# swbox_main.net
KiCad netlist of a schematic drawn in EAGLE
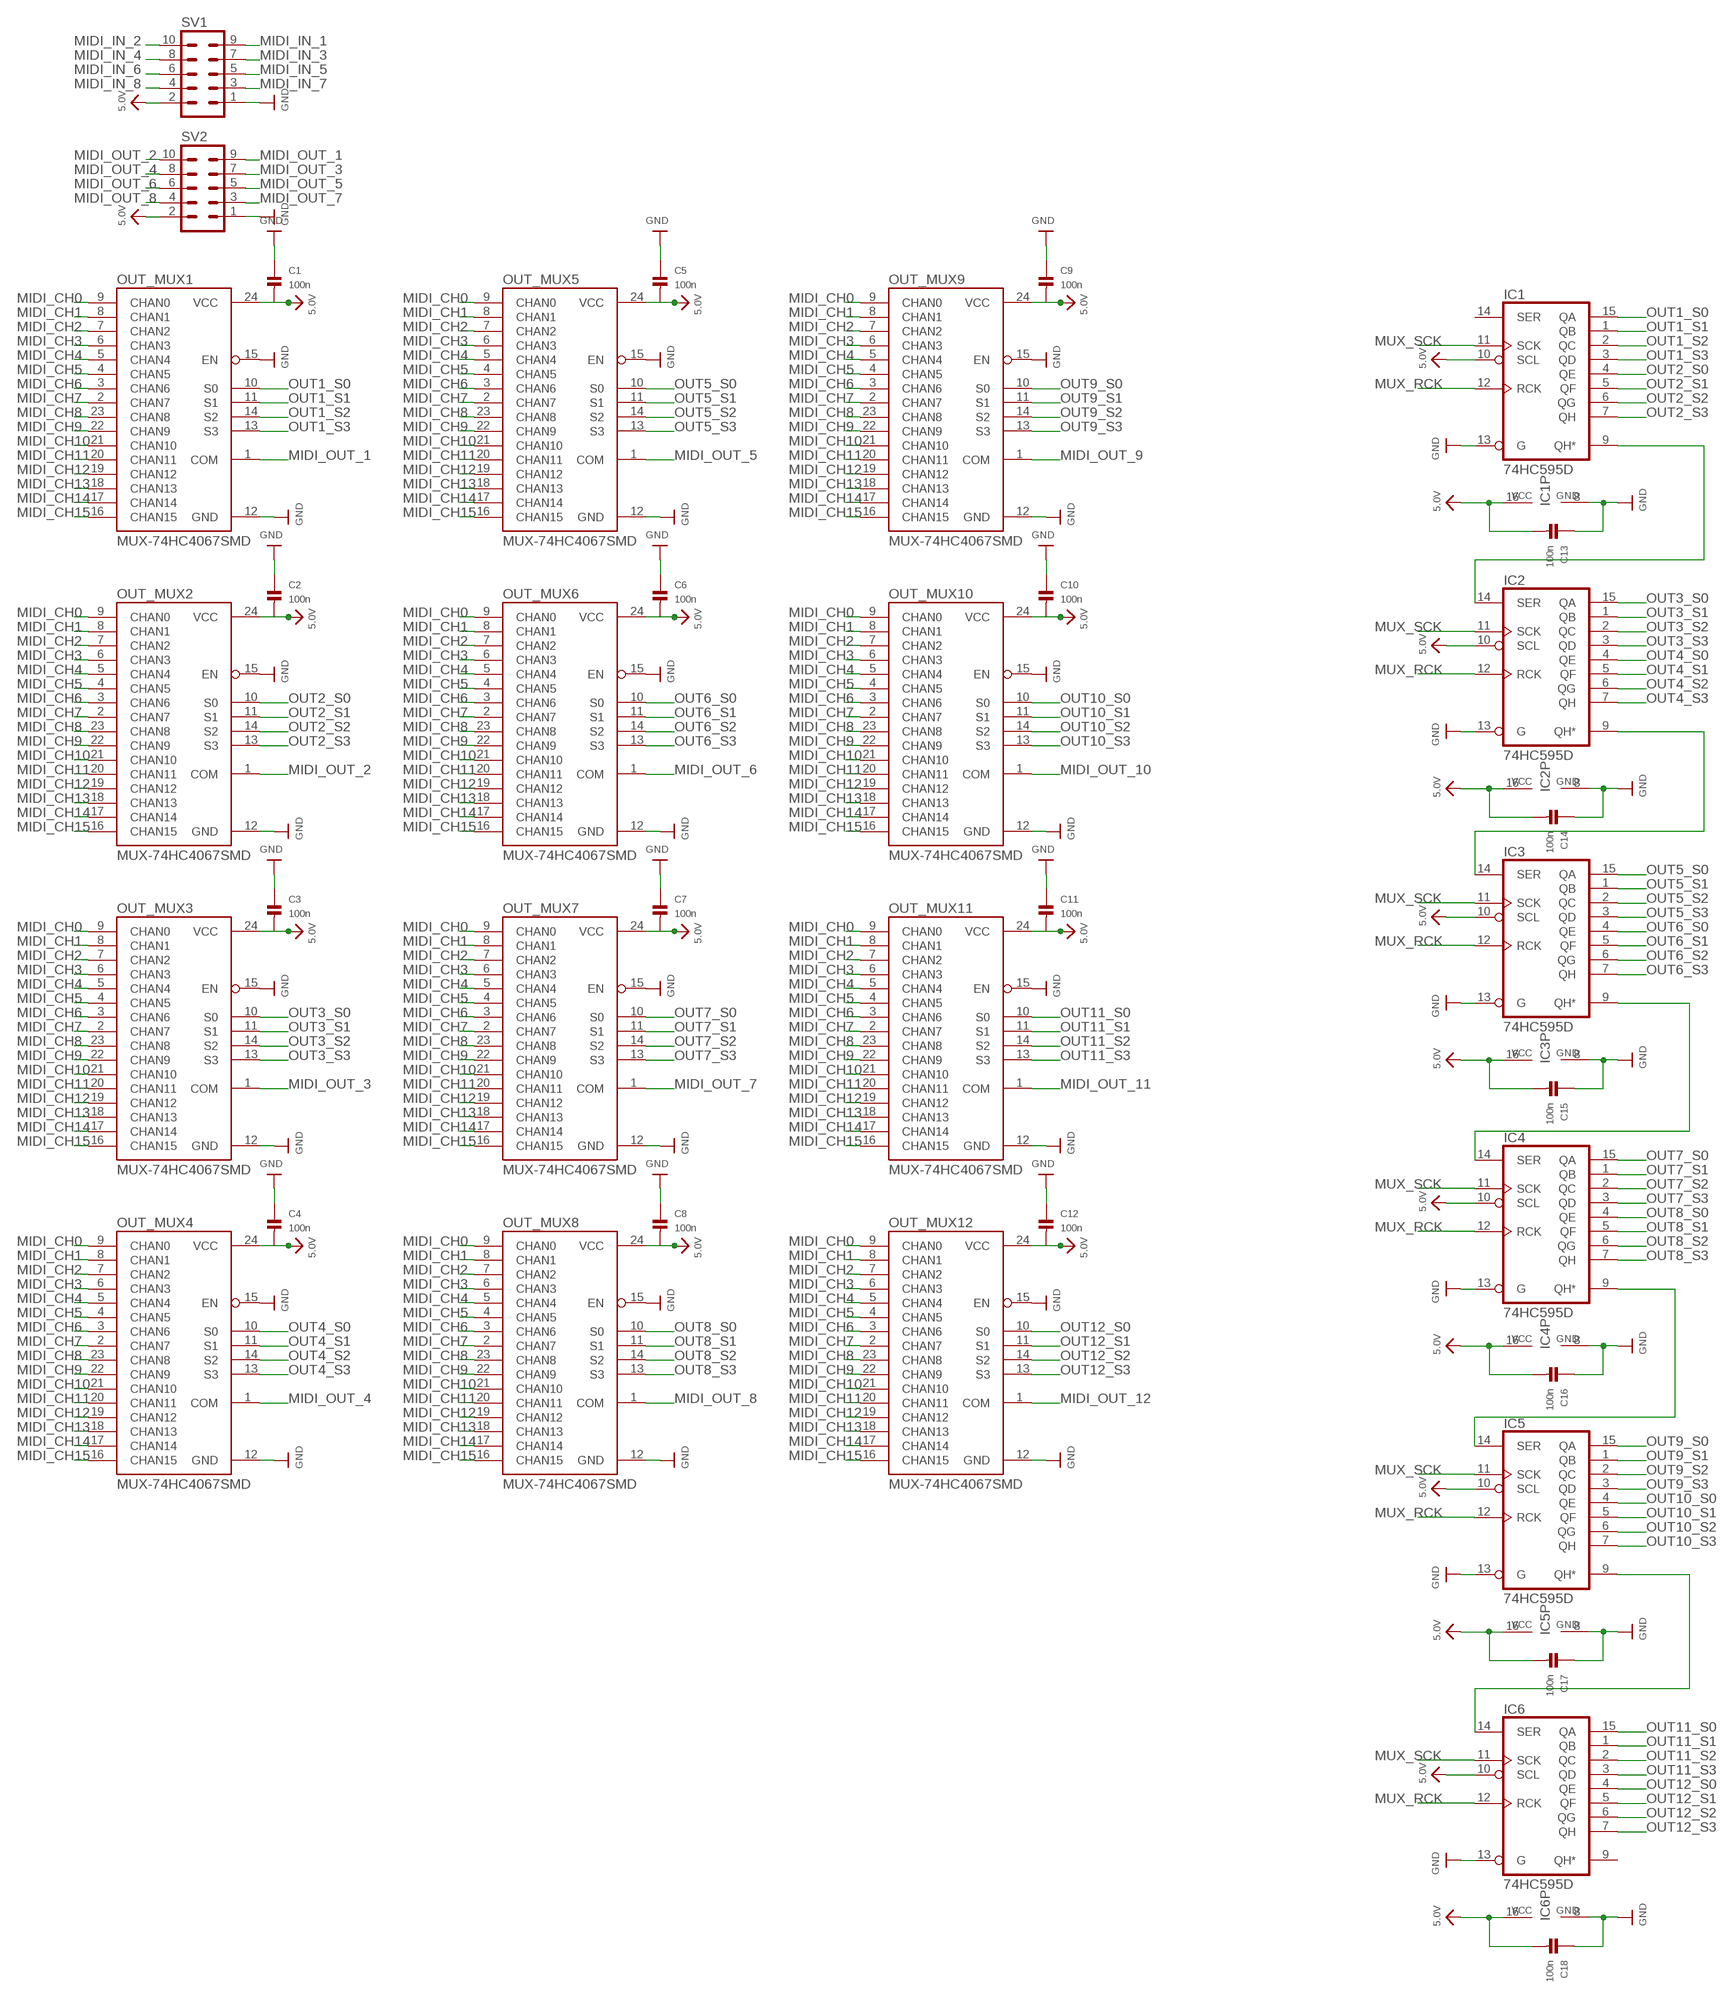
[diagram p0: schematic, sheet 1]

(export (version "E")
  (design (tool "Eeschema 10.0.6"))
  (components
    (comp (ref "C1")
      (value "100n")
      (footprint "eagle-import:0603")
      (libsource (lib "eagle-import") (part "CAP_CERAMIC0603"))
    )
    (comp (ref "C2")
      (value "100n")
      (footprint "eagle-import:0603")
      (libsource (lib "eagle-import") (part "CAP_CERAMIC0603"))
    )
    (comp (ref "C3")
      (value "100n")
      (footprint "eagle-import:0603")
      (libsource (lib "eagle-import") (part "CAP_CERAMIC0603"))
    )
    (comp (ref "C4")
      (value "100n")
      (footprint "eagle-import:0603")
      (libsource (lib "eagle-import") (part "CAP_CERAMIC0603"))
    )
    (comp (ref "C5")
      (value "100n")
      (footprint "eagle-import:0603")
      (libsource (lib "eagle-import") (part "CAP_CERAMIC0603"))
    )
    (comp (ref "C6")
      (value "100n")
      (footprint "eagle-import:0603")
      (libsource (lib "eagle-import") (part "CAP_CERAMIC0603"))
    )
    (comp (ref "C7")
      (value "100n")
      (footprint "eagle-import:0603")
      (libsource (lib "eagle-import") (part "CAP_CERAMIC0603"))
    )
    (comp (ref "C8")
      (value "100n")
      (footprint "eagle-import:0603")
      (libsource (lib "eagle-import") (part "CAP_CERAMIC0603"))
    )
    (comp (ref "C9")
      (value "100n")
      (footprint "eagle-import:0603")
      (libsource (lib "eagle-import") (part "CAP_CERAMIC0603"))
    )
    (comp (ref "C10")
      (value "100n")
      (footprint "eagle-import:0603")
      (libsource (lib "eagle-import") (part "CAP_CERAMIC0603"))
    )
    (comp (ref "C11")
      (value "100n")
      (footprint "eagle-import:0603")
      (libsource (lib "eagle-import") (part "CAP_CERAMIC0603"))
    )
    (comp (ref "C12")
      (value "100n")
      (footprint "eagle-import:0603")
      (libsource (lib "eagle-import") (part "CAP_CERAMIC0603"))
    )
    (comp (ref "C13")
      (value "100n")
      (footprint "eagle-import:0603")
      (libsource (lib "eagle-import") (part "CAP_CERAMIC0603"))
    )
    (comp (ref "C14")
      (value "100n")
      (footprint "eagle-import:0603")
      (libsource (lib "eagle-import") (part "CAP_CERAMIC0603"))
    )
    (comp (ref "C15")
      (value "100n")
      (footprint "eagle-import:0603")
      (libsource (lib "eagle-import") (part "CAP_CERAMIC0603"))
    )
    (comp (ref "C16")
      (value "100n")
      (footprint "eagle-import:0603")
      (libsource (lib "eagle-import") (part "CAP_CERAMIC0603"))
    )
    (comp (ref "C17")
      (value "100n")
      (footprint "eagle-import:0603")
      (libsource (lib "eagle-import") (part "CAP_CERAMIC0603"))
    )
    (comp (ref "C18")
      (value "100n")
      (footprint "eagle-import:0603")
      (libsource (lib "eagle-import") (part "CAP_CERAMIC0603"))
    )
    (comp (ref "IC1")
      (value "74HC595D")
      (footprint "eagle-import:SO16")
      (libsource (lib "eagle-import") (part "74595DHC"))
    )
    (comp (ref "IC2")
      (value "74HC595D")
      (footprint "eagle-import:SO16")
      (libsource (lib "eagle-import") (part "74595DHC"))
    )
    (comp (ref "IC3")
      (value "74HC595D")
      (footprint "eagle-import:SO16")
      (libsource (lib "eagle-import") (part "74595DHC"))
    )
    (comp (ref "IC4")
      (value "74HC595D")
      (footprint "eagle-import:SO16")
      (libsource (lib "eagle-import") (part "74595DHC"))
    )
    (comp (ref "IC5")
      (value "74HC595D")
      (footprint "eagle-import:SO16")
      (libsource (lib "eagle-import") (part "74595DHC"))
    )
    (comp (ref "IC6")
      (value "74HC595D")
      (footprint "eagle-import:SO16")
      (libsource (lib "eagle-import") (part "74595DHC"))
    )
    (comp (ref "OUT_MUX1")
      (value "MUX-74HC4067SMD")
      (footprint "eagle-import:SSOP24")
      (libsource (lib "eagle-import") (part "MUX-74HC4067SMD"))
    )
    (comp (ref "OUT_MUX2")
      (value "MUX-74HC4067SMD")
      (footprint "eagle-import:SSOP24")
      (libsource (lib "eagle-import") (part "MUX-74HC4067SMD"))
    )
    (comp (ref "OUT_MUX3")
      (value "MUX-74HC4067SMD")
      (footprint "eagle-import:SSOP24")
      (libsource (lib "eagle-import") (part "MUX-74HC4067SMD"))
    )
    (comp (ref "OUT_MUX4")
      (value "MUX-74HC4067SMD")
      (footprint "eagle-import:SSOP24")
      (libsource (lib "eagle-import") (part "MUX-74HC4067SMD"))
    )
    (comp (ref "OUT_MUX5")
      (value "MUX-74HC4067SMD")
      (footprint "eagle-import:SSOP24")
      (libsource (lib "eagle-import") (part "MUX-74HC4067SMD"))
    )
    (comp (ref "OUT_MUX6")
      (value "MUX-74HC4067SMD")
      (footprint "eagle-import:SSOP24")
      (libsource (lib "eagle-import") (part "MUX-74HC4067SMD"))
    )
    (comp (ref "OUT_MUX7")
      (value "MUX-74HC4067SMD")
      (footprint "eagle-import:SSOP24")
      (libsource (lib "eagle-import") (part "MUX-74HC4067SMD"))
    )
    (comp (ref "OUT_MUX8")
      (value "MUX-74HC4067SMD")
      (footprint "eagle-import:SSOP24")
      (libsource (lib "eagle-import") (part "MUX-74HC4067SMD"))
    )
    (comp (ref "OUT_MUX9")
      (value "MUX-74HC4067SMD")
      (footprint "eagle-import:SSOP24")
      (libsource (lib "eagle-import") (part "MUX-74HC4067SMD"))
    )
    (comp (ref "OUT_MUX10")
      (value "MUX-74HC4067SMD")
      (footprint "eagle-import:SSOP24")
      (libsource (lib "eagle-import") (part "MUX-74HC4067SMD"))
    )
    (comp (ref "OUT_MUX11")
      (value "MUX-74HC4067SMD")
      (footprint "eagle-import:SSOP24")
      (libsource (lib "eagle-import") (part "MUX-74HC4067SMD"))
    )
    (comp (ref "OUT_MUX12")
      (value "MUX-74HC4067SMD")
      (footprint "eagle-import:SSOP24")
      (libsource (lib "eagle-import") (part "MUX-74HC4067SMD"))
    )
    (comp (ref "SV1")
      (value "ML10")
      (footprint "eagle-import:ML10")
      (libsource (lib "eagle-import") (part "ML10"))
    )
    (comp (ref "SV2")
      (value "ML10")
      (footprint "eagle-import:ML10")
      (libsource (lib "eagle-import") (part "ML10"))
    )
  )
  (nets
    (net (code "1") (name "/MIDI_CH0") (class "Default")
      (node (ref "OUT_MUX1") (pin "9") (pinfunction "CHAN0_9") (pintype "bidirectional"))
      (node (ref "OUT_MUX10") (pin "9") (pinfunction "CHAN0_9") (pintype "bidirectional"))
      (node (ref "OUT_MUX11") (pin "9") (pinfunction "CHAN0_9") (pintype "bidirectional"))
      (node (ref "OUT_MUX12") (pin "9") (pinfunction "CHAN0_9") (pintype "bidirectional"))
      (node (ref "OUT_MUX2") (pin "9") (pinfunction "CHAN0_9") (pintype "bidirectional"))
      (node (ref "OUT_MUX3") (pin "9") (pinfunction "CHAN0_9") (pintype "bidirectional"))
      (node (ref "OUT_MUX4") (pin "9") (pinfunction "CHAN0_9") (pintype "bidirectional"))
      (node (ref "OUT_MUX5") (pin "9") (pinfunction "CHAN0_9") (pintype "bidirectional"))
      (node (ref "OUT_MUX6") (pin "9") (pinfunction "CHAN0_9") (pintype "bidirectional"))
      (node (ref "OUT_MUX7") (pin "9") (pinfunction "CHAN0_9") (pintype "bidirectional"))
      (node (ref "OUT_MUX8") (pin "9") (pinfunction "CHAN0_9") (pintype "bidirectional"))
      (node (ref "OUT_MUX9") (pin "9") (pinfunction "CHAN0_9") (pintype "bidirectional"))
    )
    (net (code "2") (name "/MIDI_CH1") (class "Default")
      (node (ref "OUT_MUX1") (pin "8") (pinfunction "CHAN1_8") (pintype "bidirectional"))
      (node (ref "OUT_MUX10") (pin "8") (pinfunction "CHAN1_8") (pintype "bidirectional"))
      (node (ref "OUT_MUX11") (pin "8") (pinfunction "CHAN1_8") (pintype "bidirectional"))
      (node (ref "OUT_MUX12") (pin "8") (pinfunction "CHAN1_8") (pintype "bidirectional"))
      (node (ref "OUT_MUX2") (pin "8") (pinfunction "CHAN1_8") (pintype "bidirectional"))
      (node (ref "OUT_MUX3") (pin "8") (pinfunction "CHAN1_8") (pintype "bidirectional"))
      (node (ref "OUT_MUX4") (pin "8") (pinfunction "CHAN1_8") (pintype "bidirectional"))
      (node (ref "OUT_MUX5") (pin "8") (pinfunction "CHAN1_8") (pintype "bidirectional"))
      (node (ref "OUT_MUX6") (pin "8") (pinfunction "CHAN1_8") (pintype "bidirectional"))
      (node (ref "OUT_MUX7") (pin "8") (pinfunction "CHAN1_8") (pintype "bidirectional"))
      (node (ref "OUT_MUX8") (pin "8") (pinfunction "CHAN1_8") (pintype "bidirectional"))
      (node (ref "OUT_MUX9") (pin "8") (pinfunction "CHAN1_8") (pintype "bidirectional"))
    )
    (net (code "3") (name "/MIDI_CH2") (class "Default")
      (node (ref "OUT_MUX1") (pin "7") (pinfunction "CHAN2_7") (pintype "bidirectional"))
      (node (ref "OUT_MUX10") (pin "7") (pinfunction "CHAN2_7") (pintype "bidirectional"))
      (node (ref "OUT_MUX11") (pin "7") (pinfunction "CHAN2_7") (pintype "bidirectional"))
      (node (ref "OUT_MUX12") (pin "7") (pinfunction "CHAN2_7") (pintype "bidirectional"))
      (node (ref "OUT_MUX2") (pin "7") (pinfunction "CHAN2_7") (pintype "bidirectional"))
      (node (ref "OUT_MUX3") (pin "7") (pinfunction "CHAN2_7") (pintype "bidirectional"))
      (node (ref "OUT_MUX4") (pin "7") (pinfunction "CHAN2_7") (pintype "bidirectional"))
      (node (ref "OUT_MUX5") (pin "7") (pinfunction "CHAN2_7") (pintype "bidirectional"))
      (node (ref "OUT_MUX6") (pin "7") (pinfunction "CHAN2_7") (pintype "bidirectional"))
      (node (ref "OUT_MUX7") (pin "7") (pinfunction "CHAN2_7") (pintype "bidirectional"))
      (node (ref "OUT_MUX8") (pin "7") (pinfunction "CHAN2_7") (pintype "bidirectional"))
      (node (ref "OUT_MUX9") (pin "7") (pinfunction "CHAN2_7") (pintype "bidirectional"))
    )
    (net (code "4") (name "/MIDI_CH3") (class "Default")
      (node (ref "OUT_MUX1") (pin "6") (pinfunction "CHAN3_6") (pintype "bidirectional"))
      (node (ref "OUT_MUX10") (pin "6") (pinfunction "CHAN3_6") (pintype "bidirectional"))
      (node (ref "OUT_MUX11") (pin "6") (pinfunction "CHAN3_6") (pintype "bidirectional"))
      (node (ref "OUT_MUX12") (pin "6") (pinfunction "CHAN3_6") (pintype "bidirectional"))
      (node (ref "OUT_MUX2") (pin "6") (pinfunction "CHAN3_6") (pintype "bidirectional"))
      (node (ref "OUT_MUX3") (pin "6") (pinfunction "CHAN3_6") (pintype "bidirectional"))
      (node (ref "OUT_MUX4") (pin "6") (pinfunction "CHAN3_6") (pintype "bidirectional"))
      (node (ref "OUT_MUX5") (pin "6") (pinfunction "CHAN3_6") (pintype "bidirectional"))
      (node (ref "OUT_MUX6") (pin "6") (pinfunction "CHAN3_6") (pintype "bidirectional"))
      (node (ref "OUT_MUX7") (pin "6") (pinfunction "CHAN3_6") (pintype "bidirectional"))
      (node (ref "OUT_MUX8") (pin "6") (pinfunction "CHAN3_6") (pintype "bidirectional"))
      (node (ref "OUT_MUX9") (pin "6") (pinfunction "CHAN3_6") (pintype "bidirectional"))
    )
    (net (code "5") (name "/MIDI_CH4") (class "Default")
      (node (ref "OUT_MUX1") (pin "5") (pinfunction "CHAN4_5") (pintype "bidirectional"))
      (node (ref "OUT_MUX10") (pin "5") (pinfunction "CHAN4_5") (pintype "bidirectional"))
      (node (ref "OUT_MUX11") (pin "5") (pinfunction "CHAN4_5") (pintype "bidirectional"))
      (node (ref "OUT_MUX12") (pin "5") (pinfunction "CHAN4_5") (pintype "bidirectional"))
      (node (ref "OUT_MUX2") (pin "5") (pinfunction "CHAN4_5") (pintype "bidirectional"))
      (node (ref "OUT_MUX3") (pin "5") (pinfunction "CHAN4_5") (pintype "bidirectional"))
      (node (ref "OUT_MUX4") (pin "5") (pinfunction "CHAN4_5") (pintype "bidirectional"))
      (node (ref "OUT_MUX5") (pin "5") (pinfunction "CHAN4_5") (pintype "bidirectional"))
      (node (ref "OUT_MUX6") (pin "5") (pinfunction "CHAN4_5") (pintype "bidirectional"))
      (node (ref "OUT_MUX7") (pin "5") (pinfunction "CHAN4_5") (pintype "bidirectional"))
      (node (ref "OUT_MUX8") (pin "5") (pinfunction "CHAN4_5") (pintype "bidirectional"))
      (node (ref "OUT_MUX9") (pin "5") (pinfunction "CHAN4_5") (pintype "bidirectional"))
    )
    (net (code "6") (name "/MIDI_CH5") (class "Default")
      (node (ref "OUT_MUX1") (pin "4") (pinfunction "CHAN5_4") (pintype "bidirectional"))
      (node (ref "OUT_MUX10") (pin "4") (pinfunction "CHAN5_4") (pintype "bidirectional"))
      (node (ref "OUT_MUX11") (pin "4") (pinfunction "CHAN5_4") (pintype "bidirectional"))
      (node (ref "OUT_MUX12") (pin "4") (pinfunction "CHAN5_4") (pintype "bidirectional"))
      (node (ref "OUT_MUX2") (pin "4") (pinfunction "CHAN5_4") (pintype "bidirectional"))
      (node (ref "OUT_MUX3") (pin "4") (pinfunction "CHAN5_4") (pintype "bidirectional"))
      (node (ref "OUT_MUX4") (pin "4") (pinfunction "CHAN5_4") (pintype "bidirectional"))
      (node (ref "OUT_MUX5") (pin "4") (pinfunction "CHAN5_4") (pintype "bidirectional"))
      (node (ref "OUT_MUX6") (pin "4") (pinfunction "CHAN5_4") (pintype "bidirectional"))
      (node (ref "OUT_MUX7") (pin "4") (pinfunction "CHAN5_4") (pintype "bidirectional"))
      (node (ref "OUT_MUX8") (pin "4") (pinfunction "CHAN5_4") (pintype "bidirectional"))
      (node (ref "OUT_MUX9") (pin "4") (pinfunction "CHAN5_4") (pintype "bidirectional"))
    )
    (net (code "7") (name "/MIDI_CH6") (class "Default")
      (node (ref "OUT_MUX1") (pin "3") (pinfunction "CHAN6_3") (pintype "bidirectional"))
      (node (ref "OUT_MUX10") (pin "3") (pinfunction "CHAN6_3") (pintype "bidirectional"))
      (node (ref "OUT_MUX11") (pin "3") (pinfunction "CHAN6_3") (pintype "bidirectional"))
      (node (ref "OUT_MUX12") (pin "3") (pinfunction "CHAN6_3") (pintype "bidirectional"))
      (node (ref "OUT_MUX2") (pin "3") (pinfunction "CHAN6_3") (pintype "bidirectional"))
      (node (ref "OUT_MUX3") (pin "3") (pinfunction "CHAN6_3") (pintype "bidirectional"))
      (node (ref "OUT_MUX4") (pin "3") (pinfunction "CHAN6_3") (pintype "bidirectional"))
      (node (ref "OUT_MUX5") (pin "3") (pinfunction "CHAN6_3") (pintype "bidirectional"))
      (node (ref "OUT_MUX6") (pin "3") (pinfunction "CHAN6_3") (pintype "bidirectional"))
      (node (ref "OUT_MUX7") (pin "3") (pinfunction "CHAN6_3") (pintype "bidirectional"))
      (node (ref "OUT_MUX8") (pin "3") (pinfunction "CHAN6_3") (pintype "bidirectional"))
      (node (ref "OUT_MUX9") (pin "3") (pinfunction "CHAN6_3") (pintype "bidirectional"))
    )
    (net (code "8") (name "/MIDI_CH7") (class "Default")
      (node (ref "OUT_MUX1") (pin "2") (pinfunction "CHAN7_2") (pintype "bidirectional"))
      (node (ref "OUT_MUX10") (pin "2") (pinfunction "CHAN7_2") (pintype "bidirectional"))
      (node (ref "OUT_MUX11") (pin "2") (pinfunction "CHAN7_2") (pintype "bidirectional"))
      (node (ref "OUT_MUX12") (pin "2") (pinfunction "CHAN7_2") (pintype "bidirectional"))
      (node (ref "OUT_MUX2") (pin "2") (pinfunction "CHAN7_2") (pintype "bidirectional"))
      (node (ref "OUT_MUX3") (pin "2") (pinfunction "CHAN7_2") (pintype "bidirectional"))
      (node (ref "OUT_MUX4") (pin "2") (pinfunction "CHAN7_2") (pintype "bidirectional"))
      (node (ref "OUT_MUX5") (pin "2") (pinfunction "CHAN7_2") (pintype "bidirectional"))
      (node (ref "OUT_MUX6") (pin "2") (pinfunction "CHAN7_2") (pintype "bidirectional"))
      (node (ref "OUT_MUX7") (pin "2") (pinfunction "CHAN7_2") (pintype "bidirectional"))
      (node (ref "OUT_MUX8") (pin "2") (pinfunction "CHAN7_2") (pintype "bidirectional"))
      (node (ref "OUT_MUX9") (pin "2") (pinfunction "CHAN7_2") (pintype "bidirectional"))
    )
    (net (code "9") (name "/MIDI_CH8") (class "Default")
      (node (ref "OUT_MUX1") (pin "23") (pinfunction "CHAN8_23") (pintype "bidirectional"))
      (node (ref "OUT_MUX10") (pin "23") (pinfunction "CHAN8_23") (pintype "bidirectional"))
      (node (ref "OUT_MUX11") (pin "23") (pinfunction "CHAN8_23") (pintype "bidirectional"))
      (node (ref "OUT_MUX12") (pin "23") (pinfunction "CHAN8_23") (pintype "bidirectional"))
      (node (ref "OUT_MUX2") (pin "23") (pinfunction "CHAN8_23") (pintype "bidirectional"))
      (node (ref "OUT_MUX3") (pin "23") (pinfunction "CHAN8_23") (pintype "bidirectional"))
      (node (ref "OUT_MUX4") (pin "23") (pinfunction "CHAN8_23") (pintype "bidirectional"))
      (node (ref "OUT_MUX5") (pin "23") (pinfunction "CHAN8_23") (pintype "bidirectional"))
      (node (ref "OUT_MUX6") (pin "23") (pinfunction "CHAN8_23") (pintype "bidirectional"))
      (node (ref "OUT_MUX7") (pin "23") (pinfunction "CHAN8_23") (pintype "bidirectional"))
      (node (ref "OUT_MUX8") (pin "23") (pinfunction "CHAN8_23") (pintype "bidirectional"))
      (node (ref "OUT_MUX9") (pin "23") (pinfunction "CHAN8_23") (pintype "bidirectional"))
    )
    (net (code "10") (name "/MIDI_CH9") (class "Default")
      (node (ref "OUT_MUX1") (pin "22") (pinfunction "CHAN9_22") (pintype "bidirectional"))
      (node (ref "OUT_MUX10") (pin "22") (pinfunction "CHAN9_22") (pintype "bidirectional"))
      (node (ref "OUT_MUX11") (pin "22") (pinfunction "CHAN9_22") (pintype "bidirectional"))
      (node (ref "OUT_MUX12") (pin "22") (pinfunction "CHAN9_22") (pintype "bidirectional"))
      (node (ref "OUT_MUX2") (pin "22") (pinfunction "CHAN9_22") (pintype "bidirectional"))
      (node (ref "OUT_MUX3") (pin "22") (pinfunction "CHAN9_22") (pintype "bidirectional"))
      (node (ref "OUT_MUX4") (pin "22") (pinfunction "CHAN9_22") (pintype "bidirectional"))
      (node (ref "OUT_MUX5") (pin "22") (pinfunction "CHAN9_22") (pintype "bidirectional"))
      (node (ref "OUT_MUX6") (pin "22") (pinfunction "CHAN9_22") (pintype "bidirectional"))
      (node (ref "OUT_MUX7") (pin "22") (pinfunction "CHAN9_22") (pintype "bidirectional"))
      (node (ref "OUT_MUX8") (pin "22") (pinfunction "CHAN9_22") (pintype "bidirectional"))
      (node (ref "OUT_MUX9") (pin "22") (pinfunction "CHAN9_22") (pintype "bidirectional"))
    )
    (net (code "11") (name "/MIDI_CH10") (class "Default")
      (node (ref "OUT_MUX1") (pin "21") (pinfunction "CHAN10_21") (pintype "bidirectional"))
      (node (ref "OUT_MUX10") (pin "21") (pinfunction "CHAN10_21") (pintype "bidirectional"))
      (node (ref "OUT_MUX11") (pin "21") (pinfunction "CHAN10_21") (pintype "bidirectional"))
      (node (ref "OUT_MUX12") (pin "21") (pinfunction "CHAN10_21") (pintype "bidirectional"))
      (node (ref "OUT_MUX2") (pin "21") (pinfunction "CHAN10_21") (pintype "bidirectional"))
      (node (ref "OUT_MUX3") (pin "21") (pinfunction "CHAN10_21") (pintype "bidirectional"))
      (node (ref "OUT_MUX4") (pin "21") (pinfunction "CHAN10_21") (pintype "bidirectional"))
      (node (ref "OUT_MUX5") (pin "21") (pinfunction "CHAN10_21") (pintype "bidirectional"))
      (node (ref "OUT_MUX6") (pin "21") (pinfunction "CHAN10_21") (pintype "bidirectional"))
      (node (ref "OUT_MUX7") (pin "21") (pinfunction "CHAN10_21") (pintype "bidirectional"))
      (node (ref "OUT_MUX8") (pin "21") (pinfunction "CHAN10_21") (pintype "bidirectional"))
      (node (ref "OUT_MUX9") (pin "21") (pinfunction "CHAN10_21") (pintype "bidirectional"))
    )
    (net (code "12") (name "/MIDI_CH11") (class "Default")
      (node (ref "OUT_MUX1") (pin "20") (pinfunction "CHAN11_20") (pintype "bidirectional"))
      (node (ref "OUT_MUX10") (pin "20") (pinfunction "CHAN11_20") (pintype "bidirectional"))
      (node (ref "OUT_MUX11") (pin "20") (pinfunction "CHAN11_20") (pintype "bidirectional"))
      (node (ref "OUT_MUX12") (pin "20") (pinfunction "CHAN11_20") (pintype "bidirectional"))
      (node (ref "OUT_MUX2") (pin "20") (pinfunction "CHAN11_20") (pintype "bidirectional"))
      (node (ref "OUT_MUX3") (pin "20") (pinfunction "CHAN11_20") (pintype "bidirectional"))
      (node (ref "OUT_MUX4") (pin "20") (pinfunction "CHAN11_20") (pintype "bidirectional"))
      (node (ref "OUT_MUX5") (pin "20") (pinfunction "CHAN11_20") (pintype "bidirectional"))
      (node (ref "OUT_MUX6") (pin "20") (pinfunction "CHAN11_20") (pintype "bidirectional"))
      (node (ref "OUT_MUX7") (pin "20") (pinfunction "CHAN11_20") (pintype "bidirectional"))
      (node (ref "OUT_MUX8") (pin "20") (pinfunction "CHAN11_20") (pintype "bidirectional"))
      (node (ref "OUT_MUX9") (pin "20") (pinfunction "CHAN11_20") (pintype "bidirectional"))
    )
    (net (code "13") (name "/MIDI_CH12") (class "Default")
      (node (ref "OUT_MUX1") (pin "19") (pinfunction "CHAN12_19") (pintype "bidirectional"))
      (node (ref "OUT_MUX10") (pin "19") (pinfunction "CHAN12_19") (pintype "bidirectional"))
      (node (ref "OUT_MUX11") (pin "19") (pinfunction "CHAN12_19") (pintype "bidirectional"))
      (node (ref "OUT_MUX12") (pin "19") (pinfunction "CHAN12_19") (pintype "bidirectional"))
      (node (ref "OUT_MUX2") (pin "19") (pinfunction "CHAN12_19") (pintype "bidirectional"))
      (node (ref "OUT_MUX3") (pin "19") (pinfunction "CHAN12_19") (pintype "bidirectional"))
      (node (ref "OUT_MUX4") (pin "19") (pinfunction "CHAN12_19") (pintype "bidirectional"))
      (node (ref "OUT_MUX5") (pin "19") (pinfunction "CHAN12_19") (pintype "bidirectional"))
      (node (ref "OUT_MUX6") (pin "19") (pinfunction "CHAN12_19") (pintype "bidirectional"))
      (node (ref "OUT_MUX7") (pin "19") (pinfunction "CHAN12_19") (pintype "bidirectional"))
      (node (ref "OUT_MUX8") (pin "19") (pinfunction "CHAN12_19") (pintype "bidirectional"))
      (node (ref "OUT_MUX9") (pin "19") (pinfunction "CHAN12_19") (pintype "bidirectional"))
    )
    (net (code "14") (name "/MIDI_CH13") (class "Default")
      (node (ref "OUT_MUX1") (pin "18") (pinfunction "CHAN13_18") (pintype "bidirectional"))
      (node (ref "OUT_MUX10") (pin "18") (pinfunction "CHAN13_18") (pintype "bidirectional"))
      (node (ref "OUT_MUX11") (pin "18") (pinfunction "CHAN13_18") (pintype "bidirectional"))
      (node (ref "OUT_MUX12") (pin "18") (pinfunction "CHAN13_18") (pintype "bidirectional"))
      (node (ref "OUT_MUX2") (pin "18") (pinfunction "CHAN13_18") (pintype "bidirectional"))
      (node (ref "OUT_MUX3") (pin "18") (pinfunction "CHAN13_18") (pintype "bidirectional"))
      (node (ref "OUT_MUX4") (pin "18") (pinfunction "CHAN13_18") (pintype "bidirectional"))
      (node (ref "OUT_MUX5") (pin "18") (pinfunction "CHAN13_18") (pintype "bidirectional"))
      (node (ref "OUT_MUX6") (pin "18") (pinfunction "CHAN13_18") (pintype "bidirectional"))
      (node (ref "OUT_MUX7") (pin "18") (pinfunction "CHAN13_18") (pintype "bidirectional"))
      (node (ref "OUT_MUX8") (pin "18") (pinfunction "CHAN13_18") (pintype "bidirectional"))
      (node (ref "OUT_MUX9") (pin "18") (pinfunction "CHAN13_18") (pintype "bidirectional"))
    )
    (net (code "15") (name "/MIDI_CH14") (class "Default")
      (node (ref "OUT_MUX1") (pin "17") (pinfunction "CHAN14_17") (pintype "bidirectional"))
      (node (ref "OUT_MUX10") (pin "17") (pinfunction "CHAN14_17") (pintype "bidirectional"))
      (node (ref "OUT_MUX11") (pin "17") (pinfunction "CHAN14_17") (pintype "bidirectional"))
      (node (ref "OUT_MUX12") (pin "17") (pinfunction "CHAN14_17") (pintype "bidirectional"))
      (node (ref "OUT_MUX2") (pin "17") (pinfunction "CHAN14_17") (pintype "bidirectional"))
      (node (ref "OUT_MUX3") (pin "17") (pinfunction "CHAN14_17") (pintype "bidirectional"))
      (node (ref "OUT_MUX4") (pin "17") (pinfunction "CHAN14_17") (pintype "bidirectional"))
      (node (ref "OUT_MUX5") (pin "17") (pinfunction "CHAN14_17") (pintype "bidirectional"))
      (node (ref "OUT_MUX6") (pin "17") (pinfunction "CHAN14_17") (pintype "bidirectional"))
      (node (ref "OUT_MUX7") (pin "17") (pinfunction "CHAN14_17") (pintype "bidirectional"))
      (node (ref "OUT_MUX8") (pin "17") (pinfunction "CHAN14_17") (pintype "bidirectional"))
      (node (ref "OUT_MUX9") (pin "17") (pinfunction "CHAN14_17") (pintype "bidirectional"))
    )
    (net (code "16") (name "/MIDI_CH15") (class "Default")
      (node (ref "OUT_MUX1") (pin "16") (pinfunction "CHAN15_16") (pintype "bidirectional"))
      (node (ref "OUT_MUX10") (pin "16") (pinfunction "CHAN15_16") (pintype "bidirectional"))
      (node (ref "OUT_MUX11") (pin "16") (pinfunction "CHAN15_16") (pintype "bidirectional"))
      (node (ref "OUT_MUX12") (pin "16") (pinfunction "CHAN15_16") (pintype "bidirectional"))
      (node (ref "OUT_MUX2") (pin "16") (pinfunction "CHAN15_16") (pintype "bidirectional"))
      (node (ref "OUT_MUX3") (pin "16") (pinfunction "CHAN15_16") (pintype "bidirectional"))
      (node (ref "OUT_MUX4") (pin "16") (pinfunction "CHAN15_16") (pintype "bidirectional"))
      (node (ref "OUT_MUX5") (pin "16") (pinfunction "CHAN15_16") (pintype "bidirectional"))
      (node (ref "OUT_MUX6") (pin "16") (pinfunction "CHAN15_16") (pintype "bidirectional"))
      (node (ref "OUT_MUX7") (pin "16") (pinfunction "CHAN15_16") (pintype "bidirectional"))
      (node (ref "OUT_MUX8") (pin "16") (pinfunction "CHAN15_16") (pintype "bidirectional"))
      (node (ref "OUT_MUX9") (pin "16") (pinfunction "CHAN15_16") (pintype "bidirectional"))
    )
    (net (code "17") (name "/MIDI_IN_1") (class "Default")
      (node (ref "SV1") (pin "9") (pinfunction "9_9") (pintype "passive"))
    )
    (net (code "18") (name "/MIDI_IN_2") (class "Default")
      (node (ref "SV1") (pin "10") (pinfunction "10_10") (pintype "passive"))
    )
    (net (code "19") (name "/MIDI_IN_3") (class "Default")
      (node (ref "SV1") (pin "7") (pinfunction "7_7") (pintype "passive"))
    )
    (net (code "20") (name "/MIDI_IN_4") (class "Default")
      (node (ref "SV1") (pin "8") (pinfunction "8_8") (pintype "passive"))
    )
    (net (code "21") (name "/MIDI_IN_5") (class "Default")
      (node (ref "SV1") (pin "5") (pinfunction "5_5") (pintype "passive"))
    )
    (net (code "22") (name "/MIDI_IN_6") (class "Default")
      (node (ref "SV1") (pin "6") (pinfunction "6_6") (pintype "passive"))
    )
    (net (code "23") (name "/MIDI_IN_7") (class "Default")
      (node (ref "SV1") (pin "3") (pinfunction "3_3") (pintype "passive"))
    )
    (net (code "24") (name "/MIDI_IN_8") (class "Default")
      (node (ref "SV1") (pin "4") (pinfunction "4_4") (pintype "passive"))
    )
    (net (code "25") (name "/MIDI_OUT_1") (class "Default")
      (node (ref "OUT_MUX1") (pin "1") (pinfunction "COM_1") (pintype "bidirectional"))
      (node (ref "SV2") (pin "9") (pinfunction "9_9") (pintype "passive"))
    )
    (net (code "26") (name "/MIDI_OUT_2") (class "Default")
      (node (ref "OUT_MUX2") (pin "1") (pinfunction "COM_1") (pintype "bidirectional"))
      (node (ref "SV2") (pin "10") (pinfunction "10_10") (pintype "passive"))
    )
    (net (code "27") (name "/MIDI_OUT_3") (class "Default")
      (node (ref "OUT_MUX3") (pin "1") (pinfunction "COM_1") (pintype "bidirectional"))
      (node (ref "SV2") (pin "7") (pinfunction "7_7") (pintype "passive"))
    )
    (net (code "28") (name "/MIDI_OUT_4") (class "Default")
      (node (ref "OUT_MUX4") (pin "1") (pinfunction "COM_1") (pintype "bidirectional"))
      (node (ref "SV2") (pin "8") (pinfunction "8_8") (pintype "passive"))
    )
    (net (code "29") (name "/MIDI_OUT_5") (class "Default")
      (node (ref "OUT_MUX5") (pin "1") (pinfunction "COM_1") (pintype "bidirectional"))
      (node (ref "SV2") (pin "5") (pinfunction "5_5") (pintype "passive"))
    )
    (net (code "30") (name "/MIDI_OUT_6") (class "Default")
      (node (ref "OUT_MUX6") (pin "1") (pinfunction "COM_1") (pintype "bidirectional"))
      (node (ref "SV2") (pin "6") (pinfunction "6_6") (pintype "passive"))
    )
    (net (code "31") (name "/MIDI_OUT_7") (class "Default")
      (node (ref "OUT_MUX7") (pin "1") (pinfunction "COM_1") (pintype "bidirectional"))
      (node (ref "SV2") (pin "3") (pinfunction "3_3") (pintype "passive"))
    )
    (net (code "32") (name "/MIDI_OUT_8") (class "Default")
      (node (ref "OUT_MUX8") (pin "1") (pinfunction "COM_1") (pintype "bidirectional"))
      (node (ref "SV2") (pin "4") (pinfunction "4_4") (pintype "passive"))
    )
    (net (code "33") (name "/MIDI_OUT_9") (class "Default")
      (node (ref "OUT_MUX9") (pin "1") (pinfunction "COM_1") (pintype "bidirectional"))
    )
    (net (code "34") (name "/MIDI_OUT_10") (class "Default")
      (node (ref "OUT_MUX10") (pin "1") (pinfunction "COM_1") (pintype "bidirectional"))
    )
    (net (code "35") (name "/MIDI_OUT_11") (class "Default")
      (node (ref "OUT_MUX11") (pin "1") (pinfunction "COM_1") (pintype "bidirectional"))
    )
    (net (code "36") (name "/MIDI_OUT_12") (class "Default")
      (node (ref "OUT_MUX12") (pin "1") (pinfunction "COM_1") (pintype "bidirectional"))
    )
    (net (code "37") (name "/MUX_RCK") (class "Default")
      (node (ref "IC1") (pin "12") (pinfunction "RCK_12") (pintype "input"))
      (node (ref "IC2") (pin "12") (pinfunction "RCK_12") (pintype "input"))
      (node (ref "IC3") (pin "12") (pinfunction "RCK_12") (pintype "input"))
      (node (ref "IC4") (pin "12") (pinfunction "RCK_12") (pintype "input"))
      (node (ref "IC5") (pin "12") (pinfunction "RCK_12") (pintype "input"))
      (node (ref "IC6") (pin "12") (pinfunction "RCK_12") (pintype "input"))
    )
    (net (code "38") (name "/MUX_SCK") (class "Default")
      (node (ref "IC1") (pin "11") (pinfunction "SCK_11") (pintype "input"))
      (node (ref "IC2") (pin "11") (pinfunction "SCK_11") (pintype "input"))
      (node (ref "IC3") (pin "11") (pinfunction "SCK_11") (pintype "input"))
      (node (ref "IC4") (pin "11") (pinfunction "SCK_11") (pintype "input"))
      (node (ref "IC5") (pin "11") (pinfunction "SCK_11") (pintype "input"))
      (node (ref "IC6") (pin "11") (pinfunction "SCK_11") (pintype "input"))
    )
    (net (code "39") (name "/OUT1_S0") (class "Default")
      (node (ref "IC1") (pin "15") (pinfunction "QA_15") (pintype "tri_state"))
      (node (ref "OUT_MUX1") (pin "10") (pinfunction "S0_10") (pintype "input"))
    )
    (net (code "40") (name "/OUT1_S1") (class "Default")
      (node (ref "IC1") (pin "1") (pinfunction "QB_1") (pintype "tri_state"))
      (node (ref "OUT_MUX1") (pin "11") (pinfunction "S1_11") (pintype "input"))
    )
    (net (code "41") (name "/OUT1_S2") (class "Default")
      (node (ref "IC1") (pin "2") (pinfunction "QC_2") (pintype "tri_state"))
      (node (ref "OUT_MUX1") (pin "14") (pinfunction "S2_14") (pintype "input"))
    )
    (net (code "42") (name "/OUT1_S3") (class "Default")
      (node (ref "IC1") (pin "3") (pinfunction "QD_3") (pintype "tri_state"))
      (node (ref "OUT_MUX1") (pin "13") (pinfunction "S3_13") (pintype "input"))
    )
    (net (code "43") (name "/OUT2_S0") (class "Default")
      (node (ref "IC1") (pin "4") (pinfunction "QE_4") (pintype "tri_state"))
      (node (ref "OUT_MUX2") (pin "10") (pinfunction "S0_10") (pintype "input"))
    )
    (net (code "44") (name "/OUT2_S1") (class "Default")
      (node (ref "IC1") (pin "5") (pinfunction "QF_5") (pintype "tri_state"))
      (node (ref "OUT_MUX2") (pin "11") (pinfunction "S1_11") (pintype "input"))
    )
    (net (code "45") (name "/OUT2_S2") (class "Default")
      (node (ref "IC1") (pin "6") (pinfunction "QG_6") (pintype "tri_state"))
      (node (ref "OUT_MUX2") (pin "14") (pinfunction "S2_14") (pintype "input"))
    )
    (net (code "46") (name "/OUT2_S3") (class "Default")
      (node (ref "IC1") (pin "7") (pinfunction "QH_7") (pintype "tri_state"))
      (node (ref "OUT_MUX2") (pin "13") (pinfunction "S3_13") (pintype "input"))
    )
    (net (code "47") (name "/OUT3_S0") (class "Default")
      (node (ref "IC2") (pin "15") (pinfunction "QA_15") (pintype "tri_state"))
      (node (ref "OUT_MUX3") (pin "10") (pinfunction "S0_10") (pintype "input"))
    )
    (net (code "48") (name "/OUT3_S1") (class "Default")
      (node (ref "IC2") (pin "1") (pinfunction "QB_1") (pintype "tri_state"))
      (node (ref "OUT_MUX3") (pin "11") (pinfunction "S1_11") (pintype "input"))
    )
    (net (code "49") (name "/OUT3_S2") (class "Default")
      (node (ref "IC2") (pin "2") (pinfunction "QC_2") (pintype "tri_state"))
      (node (ref "OUT_MUX3") (pin "14") (pinfunction "S2_14") (pintype "input"))
    )
    (net (code "50") (name "/OUT3_S3") (class "Default")
      (node (ref "IC2") (pin "3") (pinfunction "QD_3") (pintype "tri_state"))
      (node (ref "OUT_MUX3") (pin "13") (pinfunction "S3_13") (pintype "input"))
    )
    (net (code "51") (name "/OUT4_S0") (class "Default")
      (node (ref "IC2") (pin "4") (pinfunction "QE_4") (pintype "tri_state"))
      (node (ref "OUT_MUX4") (pin "10") (pinfunction "S0_10") (pintype "input"))
    )
    (net (code "52") (name "/OUT4_S1") (class "Default")
      (node (ref "IC2") (pin "5") (pinfunction "QF_5") (pintype "tri_state"))
      (node (ref "OUT_MUX4") (pin "11") (pinfunction "S1_11") (pintype "input"))
    )
    (net (code "53") (name "/OUT4_S2") (class "Default")
      (node (ref "IC2") (pin "6") (pinfunction "QG_6") (pintype "tri_state"))
      (node (ref "OUT_MUX4") (pin "14") (pinfunction "S2_14") (pintype "input"))
    )
    (net (code "54") (name "/OUT4_S3") (class "Default")
      (node (ref "IC2") (pin "7") (pinfunction "QH_7") (pintype "tri_state"))
      (node (ref "OUT_MUX4") (pin "13") (pinfunction "S3_13") (pintype "input"))
    )
    (net (code "55") (name "/OUT5_S0") (class "Default")
      (node (ref "IC3") (pin "15") (pinfunction "QA_15") (pintype "tri_state"))
      (node (ref "OUT_MUX5") (pin "10") (pinfunction "S0_10") (pintype "input"))
    )
    (net (code "56") (name "/OUT5_S1") (class "Default")
      (node (ref "IC3") (pin "1") (pinfunction "QB_1") (pintype "tri_state"))
      (node (ref "OUT_MUX5") (pin "11") (pinfunction "S1_11") (pintype "input"))
    )
    (net (code "57") (name "/OUT5_S2") (class "Default")
      (node (ref "IC3") (pin "2") (pinfunction "QC_2") (pintype "tri_state"))
      (node (ref "OUT_MUX5") (pin "14") (pinfunction "S2_14") (pintype "input"))
    )
    (net (code "58") (name "/OUT5_S3") (class "Default")
      (node (ref "IC3") (pin "3") (pinfunction "QD_3") (pintype "tri_state"))
      (node (ref "OUT_MUX5") (pin "13") (pinfunction "S3_13") (pintype "input"))
    )
    (net (code "59") (name "/OUT6_S0") (class "Default")
      (node (ref "IC3") (pin "4") (pinfunction "QE_4") (pintype "tri_state"))
      (node (ref "OUT_MUX6") (pin "10") (pinfunction "S0_10") (pintype "input"))
    )
    (net (code "60") (name "/OUT6_S1") (class "Default")
      (node (ref "IC3") (pin "5") (pinfunction "QF_5") (pintype "tri_state"))
      (node (ref "OUT_MUX6") (pin "11") (pinfunction "S1_11") (pintype "input"))
    )
    (net (code "61") (name "/OUT6_S2") (class "Default")
      (node (ref "IC3") (pin "6") (pinfunction "QG_6") (pintype "tri_state"))
      (node (ref "OUT_MUX6") (pin "14") (pinfunction "S2_14") (pintype "input"))
    )
    (net (code "62") (name "/OUT6_S3") (class "Default")
      (node (ref "IC3") (pin "7") (pinfunction "QH_7") (pintype "tri_state"))
      (node (ref "OUT_MUX6") (pin "13") (pinfunction "S3_13") (pintype "input"))
    )
    (net (code "63") (name "/OUT7_S0") (class "Default")
      (node (ref "IC4") (pin "15") (pinfunction "QA_15") (pintype "tri_state"))
      (node (ref "OUT_MUX7") (pin "10") (pinfunction "S0_10") (pintype "input"))
    )
    (net (code "64") (name "/OUT7_S1") (class "Default")
      (node (ref "IC4") (pin "1") (pinfunction "QB_1") (pintype "tri_state"))
      (node (ref "OUT_MUX7") (pin "11") (pinfunction "S1_11") (pintype "input"))
    )
    (net (code "65") (name "/OUT7_S2") (class "Default")
      (node (ref "IC4") (pin "2") (pinfunction "QC_2") (pintype "tri_state"))
      (node (ref "OUT_MUX7") (pin "14") (pinfunction "S2_14") (pintype "input"))
    )
    (net (code "66") (name "/OUT7_S3") (class "Default")
      (node (ref "IC4") (pin "3") (pinfunction "QD_3") (pintype "tri_state"))
      (node (ref "OUT_MUX7") (pin "13") (pinfunction "S3_13") (pintype "input"))
    )
    (net (code "67") (name "/OUT8_S0") (class "Default")
      (node (ref "IC4") (pin "4") (pinfunction "QE_4") (pintype "tri_state"))
      (node (ref "OUT_MUX8") (pin "10") (pinfunction "S0_10") (pintype "input"))
    )
    (net (code "68") (name "/OUT8_S1") (class "Default")
      (node (ref "IC4") (pin "5") (pinfunction "QF_5") (pintype "tri_state"))
      (node (ref "OUT_MUX8") (pin "11") (pinfunction "S1_11") (pintype "input"))
    )
    (net (code "69") (name "/OUT8_S2") (class "Default")
      (node (ref "IC4") (pin "6") (pinfunction "QG_6") (pintype "tri_state"))
      (node (ref "OUT_MUX8") (pin "14") (pinfunction "S2_14") (pintype "input"))
    )
    (net (code "70") (name "/OUT8_S3") (class "Default")
      (node (ref "IC4") (pin "7") (pinfunction "QH_7") (pintype "tri_state"))
      (node (ref "OUT_MUX8") (pin "13") (pinfunction "S3_13") (pintype "input"))
    )
    (net (code "71") (name "/OUT9_S0") (class "Default")
      (node (ref "IC5") (pin "15") (pinfunction "QA_15") (pintype "tri_state"))
      (node (ref "OUT_MUX9") (pin "10") (pinfunction "S0_10") (pintype "input"))
    )
    (net (code "72") (name "/OUT9_S1") (class "Default")
      (node (ref "IC5") (pin "1") (pinfunction "QB_1") (pintype "tri_state"))
      (node (ref "OUT_MUX9") (pin "11") (pinfunction "S1_11") (pintype "input"))
    )
    (net (code "73") (name "/OUT9_S2") (class "Default")
      (node (ref "IC5") (pin "2") (pinfunction "QC_2") (pintype "tri_state"))
      (node (ref "OUT_MUX9") (pin "14") (pinfunction "S2_14") (pintype "input"))
    )
    (net (code "74") (name "/OUT9_S3") (class "Default")
      (node (ref "IC5") (pin "3") (pinfunction "QD_3") (pintype "tri_state"))
      (node (ref "OUT_MUX9") (pin "13") (pinfunction "S3_13") (pintype "input"))
    )
    (net (code "75") (name "/OUT10_S0") (class "Default")
      (node (ref "IC5") (pin "4") (pinfunction "QE_4") (pintype "tri_state"))
      (node (ref "OUT_MUX10") (pin "10") (pinfunction "S0_10") (pintype "input"))
    )
    (net (code "76") (name "/OUT10_S1") (class "Default")
      (node (ref "IC5") (pin "5") (pinfunction "QF_5") (pintype "tri_state"))
      (node (ref "OUT_MUX10") (pin "11") (pinfunction "S1_11") (pintype "input"))
    )
    (net (code "77") (name "/OUT10_S2") (class "Default")
      (node (ref "IC5") (pin "6") (pinfunction "QG_6") (pintype "tri_state"))
      (node (ref "OUT_MUX10") (pin "14") (pinfunction "S2_14") (pintype "input"))
    )
    (net (code "78") (name "/OUT10_S3") (class "Default")
      (node (ref "IC5") (pin "7") (pinfunction "QH_7") (pintype "tri_state"))
      (node (ref "OUT_MUX10") (pin "13") (pinfunction "S3_13") (pintype "input"))
    )
    (net (code "79") (name "/OUT11_S0") (class "Default")
      (node (ref "IC6") (pin "15") (pinfunction "QA_15") (pintype "tri_state"))
      (node (ref "OUT_MUX11") (pin "10") (pinfunction "S0_10") (pintype "input"))
    )
    (net (code "80") (name "/OUT11_S1") (class "Default")
      (node (ref "IC6") (pin "1") (pinfunction "QB_1") (pintype "tri_state"))
      (node (ref "OUT_MUX11") (pin "11") (pinfunction "S1_11") (pintype "input"))
    )
    (net (code "81") (name "/OUT11_S2") (class "Default")
      (node (ref "IC6") (pin "2") (pinfunction "QC_2") (pintype "tri_state"))
      (node (ref "OUT_MUX11") (pin "14") (pinfunction "S2_14") (pintype "input"))
    )
    (net (code "82") (name "/OUT11_S3") (class "Default")
      (node (ref "IC6") (pin "3") (pinfunction "QD_3") (pintype "tri_state"))
      (node (ref "OUT_MUX11") (pin "13") (pinfunction "S3_13") (pintype "input"))
    )
    (net (code "83") (name "/OUT12_S0") (class "Default")
      (node (ref "IC6") (pin "4") (pinfunction "QE_4") (pintype "tri_state"))
      (node (ref "OUT_MUX12") (pin "10") (pinfunction "S0_10") (pintype "input"))
    )
    (net (code "84") (name "/OUT12_S1") (class "Default")
      (node (ref "IC6") (pin "5") (pinfunction "QF_5") (pintype "tri_state"))
      (node (ref "OUT_MUX12") (pin "11") (pinfunction "S1_11") (pintype "input"))
    )
    (net (code "85") (name "/OUT12_S2") (class "Default")
      (node (ref "IC6") (pin "6") (pinfunction "QG_6") (pintype "tri_state"))
      (node (ref "OUT_MUX12") (pin "14") (pinfunction "S2_14") (pintype "input"))
    )
    (net (code "86") (name "/OUT12_S3") (class "Default")
      (node (ref "IC6") (pin "7") (pinfunction "QH_7") (pintype "tri_state"))
      (node (ref "OUT_MUX12") (pin "13") (pinfunction "S3_13") (pintype "input"))
    )
    (net (code "87") (name "5.0V") (class "Default")
      (node (ref "C1") (pin "2") (pinfunction "P$2_2") (pintype "passive"))
      (node (ref "C10") (pin "2") (pinfunction "P$2_2") (pintype "passive"))
      (node (ref "C11") (pin "2") (pinfunction "P$2_2") (pintype "passive"))
      (node (ref "C12") (pin "2") (pinfunction "P$2_2") (pintype "passive"))
      (node (ref "C13") (pin "2") (pinfunction "P$2_2") (pintype "passive"))
      (node (ref "C14") (pin "2") (pinfunction "P$2_2") (pintype "passive"))
      (node (ref "C15") (pin "2") (pinfunction "P$2_2") (pintype "passive"))
      (node (ref "C16") (pin "2") (pinfunction "P$2_2") (pintype "passive"))
      (node (ref "C17") (pin "2") (pinfunction "P$2_2") (pintype "passive"))
      (node (ref "C18") (pin "2") (pinfunction "P$2_2") (pintype "passive"))
      (node (ref "C2") (pin "2") (pinfunction "P$2_2") (pintype "passive"))
      (node (ref "C3") (pin "2") (pinfunction "P$2_2") (pintype "passive"))
      (node (ref "C4") (pin "2") (pinfunction "P$2_2") (pintype "passive"))
      (node (ref "C5") (pin "2") (pinfunction "P$2_2") (pintype "passive"))
      (node (ref "C6") (pin "2") (pinfunction "P$2_2") (pintype "passive"))
      (node (ref "C7") (pin "2") (pinfunction "P$2_2") (pintype "passive"))
      (node (ref "C8") (pin "2") (pinfunction "P$2_2") (pintype "passive"))
      (node (ref "C9") (pin "2") (pinfunction "P$2_2") (pintype "passive"))
      (node (ref "IC1") (pin "10") (pinfunction "SCL_10") (pintype "input"))
      (node (ref "IC1") (pin "16") (pinfunction "VCC_16") (pintype "power_in"))
      (node (ref "IC2") (pin "10") (pinfunction "SCL_10") (pintype "input"))
      (node (ref "IC2") (pin "16") (pinfunction "VCC_16") (pintype "power_in"))
      (node (ref "IC3") (pin "10") (pinfunction "SCL_10") (pintype "input"))
      (node (ref "IC3") (pin "16") (pinfunction "VCC_16") (pintype "power_in"))
      (node (ref "IC4") (pin "10") (pinfunction "SCL_10") (pintype "input"))
      (node (ref "IC4") (pin "16") (pinfunction "VCC_16") (pintype "power_in"))
      (node (ref "IC5") (pin "10") (pinfunction "SCL_10") (pintype "input"))
      (node (ref "IC5") (pin "16") (pinfunction "VCC_16") (pintype "power_in"))
      (node (ref "IC6") (pin "10") (pinfunction "SCL_10") (pintype "input"))
      (node (ref "IC6") (pin "16") (pinfunction "VCC_16") (pintype "power_in"))
      (node (ref "OUT_MUX1") (pin "24") (pinfunction "VCC_24") (pintype "bidirectional"))
      (node (ref "OUT_MUX10") (pin "24") (pinfunction "VCC_24") (pintype "bidirectional"))
      (node (ref "OUT_MUX11") (pin "24") (pinfunction "VCC_24") (pintype "bidirectional"))
      (node (ref "OUT_MUX12") (pin "24") (pinfunction "VCC_24") (pintype "bidirectional"))
      (node (ref "OUT_MUX2") (pin "24") (pinfunction "VCC_24") (pintype "bidirectional"))
      (node (ref "OUT_MUX3") (pin "24") (pinfunction "VCC_24") (pintype "bidirectional"))
      (node (ref "OUT_MUX4") (pin "24") (pinfunction "VCC_24") (pintype "bidirectional"))
      (node (ref "OUT_MUX5") (pin "24") (pinfunction "VCC_24") (pintype "bidirectional"))
      (node (ref "OUT_MUX6") (pin "24") (pinfunction "VCC_24") (pintype "bidirectional"))
      (node (ref "OUT_MUX7") (pin "24") (pinfunction "VCC_24") (pintype "bidirectional"))
      (node (ref "OUT_MUX8") (pin "24") (pinfunction "VCC_24") (pintype "bidirectional"))
      (node (ref "OUT_MUX9") (pin "24") (pinfunction "VCC_24") (pintype "bidirectional"))
      (node (ref "SV1") (pin "2") (pinfunction "2_2") (pintype "passive"))
      (node (ref "SV2") (pin "2") (pinfunction "2_2") (pintype "passive"))
    )
    (net (code "88") (name "GND") (class "Default")
      (node (ref "C1") (pin "1") (pinfunction "P$1_1") (pintype "passive"))
      (node (ref "C10") (pin "1") (pinfunction "P$1_1") (pintype "passive"))
      (node (ref "C11") (pin "1") (pinfunction "P$1_1") (pintype "passive"))
      (node (ref "C12") (pin "1") (pinfunction "P$1_1") (pintype "passive"))
      (node (ref "C13") (pin "1") (pinfunction "P$1_1") (pintype "passive"))
      (node (ref "C14") (pin "1") (pinfunction "P$1_1") (pintype "passive"))
      (node (ref "C15") (pin "1") (pinfunction "P$1_1") (pintype "passive"))
      (node (ref "C16") (pin "1") (pinfunction "P$1_1") (pintype "passive"))
      (node (ref "C17") (pin "1") (pinfunction "P$1_1") (pintype "passive"))
      (node (ref "C18") (pin "1") (pinfunction "P$1_1") (pintype "passive"))
      (node (ref "C2") (pin "1") (pinfunction "P$1_1") (pintype "passive"))
      (node (ref "C3") (pin "1") (pinfunction "P$1_1") (pintype "passive"))
      (node (ref "C4") (pin "1") (pinfunction "P$1_1") (pintype "passive"))
      (node (ref "C5") (pin "1") (pinfunction "P$1_1") (pintype "passive"))
      (node (ref "C6") (pin "1") (pinfunction "P$1_1") (pintype "passive"))
      (node (ref "C7") (pin "1") (pinfunction "P$1_1") (pintype "passive"))
      (node (ref "C8") (pin "1") (pinfunction "P$1_1") (pintype "passive"))
      (node (ref "C9") (pin "1") (pinfunction "P$1_1") (pintype "passive"))
      (node (ref "IC1") (pin "13") (pinfunction "G_13") (pintype "input"))
      (node (ref "IC1") (pin "8") (pinfunction "GND_8") (pintype "power_in"))
      (node (ref "IC2") (pin "13") (pinfunction "G_13") (pintype "input"))
      (node (ref "IC2") (pin "8") (pinfunction "GND_8") (pintype "power_in"))
      (node (ref "IC3") (pin "13") (pinfunction "G_13") (pintype "input"))
      (node (ref "IC3") (pin "8") (pinfunction "GND_8") (pintype "power_in"))
      (node (ref "IC4") (pin "13") (pinfunction "G_13") (pintype "input"))
      (node (ref "IC4") (pin "8") (pinfunction "GND_8") (pintype "power_in"))
      (node (ref "IC5") (pin "13") (pinfunction "G_13") (pintype "input"))
      (node (ref "IC5") (pin "8") (pinfunction "GND_8") (pintype "power_in"))
      (node (ref "IC6") (pin "13") (pinfunction "G_13") (pintype "input"))
      (node (ref "IC6") (pin "8") (pinfunction "GND_8") (pintype "power_in"))
      (node (ref "OUT_MUX1") (pin "12") (pinfunction "GND_12") (pintype "bidirectional"))
      (node (ref "OUT_MUX1") (pin "15") (pinfunction "EN_15") (pintype "input"))
      (node (ref "OUT_MUX10") (pin "12") (pinfunction "GND_12") (pintype "bidirectional"))
      (node (ref "OUT_MUX10") (pin "15") (pinfunction "EN_15") (pintype "input"))
      (node (ref "OUT_MUX11") (pin "12") (pinfunction "GND_12") (pintype "bidirectional"))
      (node (ref "OUT_MUX11") (pin "15") (pinfunction "EN_15") (pintype "input"))
      (node (ref "OUT_MUX12") (pin "12") (pinfunction "GND_12") (pintype "bidirectional"))
      (node (ref "OUT_MUX12") (pin "15") (pinfunction "EN_15") (pintype "input"))
      (node (ref "OUT_MUX2") (pin "12") (pinfunction "GND_12") (pintype "bidirectional"))
      (node (ref "OUT_MUX2") (pin "15") (pinfunction "EN_15") (pintype "input"))
      (node (ref "OUT_MUX3") (pin "12") (pinfunction "GND_12") (pintype "bidirectional"))
      (node (ref "OUT_MUX3") (pin "15") (pinfunction "EN_15") (pintype "input"))
      (node (ref "OUT_MUX4") (pin "12") (pinfunction "GND_12") (pintype "bidirectional"))
      (node (ref "OUT_MUX4") (pin "15") (pinfunction "EN_15") (pintype "input"))
      (node (ref "OUT_MUX5") (pin "12") (pinfunction "GND_12") (pintype "bidirectional"))
      (node (ref "OUT_MUX5") (pin "15") (pinfunction "EN_15") (pintype "input"))
      (node (ref "OUT_MUX6") (pin "12") (pinfunction "GND_12") (pintype "bidirectional"))
      (node (ref "OUT_MUX6") (pin "15") (pinfunction "EN_15") (pintype "input"))
      (node (ref "OUT_MUX7") (pin "12") (pinfunction "GND_12") (pintype "bidirectional"))
      (node (ref "OUT_MUX7") (pin "15") (pinfunction "EN_15") (pintype "input"))
      (node (ref "OUT_MUX8") (pin "12") (pinfunction "GND_12") (pintype "bidirectional"))
      (node (ref "OUT_MUX8") (pin "15") (pinfunction "EN_15") (pintype "input"))
      (node (ref "OUT_MUX9") (pin "12") (pinfunction "GND_12") (pintype "bidirectional"))
      (node (ref "OUT_MUX9") (pin "15") (pinfunction "EN_15") (pintype "input"))
      (node (ref "SV1") (pin "1") (pinfunction "1_1") (pintype "passive"))
      (node (ref "SV2") (pin "1") (pinfunction "1_1") (pintype "passive"))
    )
    (net (code "89") (name "Net-(IC1A-QH*)") (class "Default")
      (node (ref "IC1") (pin "9") (pinfunction "QH*_9") (pintype "tri_state"))
      (node (ref "IC2") (pin "14") (pinfunction "SER_14") (pintype "input"))
    )
    (net (code "90") (name "Net-(IC2A-QH*)") (class "Default")
      (node (ref "IC2") (pin "9") (pinfunction "QH*_9") (pintype "tri_state"))
      (node (ref "IC3") (pin "14") (pinfunction "SER_14") (pintype "input"))
    )
    (net (code "91") (name "Net-(IC3A-QH*)") (class "Default")
      (node (ref "IC3") (pin "9") (pinfunction "QH*_9") (pintype "tri_state"))
      (node (ref "IC4") (pin "14") (pinfunction "SER_14") (pintype "input"))
    )
    (net (code "92") (name "Net-(IC4A-QH*)") (class "Default")
      (node (ref "IC4") (pin "9") (pinfunction "QH*_9") (pintype "tri_state"))
      (node (ref "IC5") (pin "14") (pinfunction "SER_14") (pintype "input"))
    )
    (net (code "93") (name "Net-(IC5A-QH*)") (class "Default")
      (node (ref "IC5") (pin "9") (pinfunction "QH*_9") (pintype "tri_state"))
      (node (ref "IC6") (pin "14") (pinfunction "SER_14") (pintype "input"))
    )
    (net (code "94") (name "unconnected-(IC1A-SER-Pad14)") (class "Default")
      (node (ref "IC1") (pin "14") (pinfunction "SER_14") (pintype "input"))
    )
    (net (code "95") (name "unconnected-(IC6A-QH*-Pad9)") (class "Default")
      (node (ref "IC6") (pin "9") (pinfunction "QH*_9") (pintype "tri_state"))
    )
  )
)
